# PCA_0006_Mini_CB_Servo_REV_B.net
KiCad netlist of a schematic drawn in Altium Designer
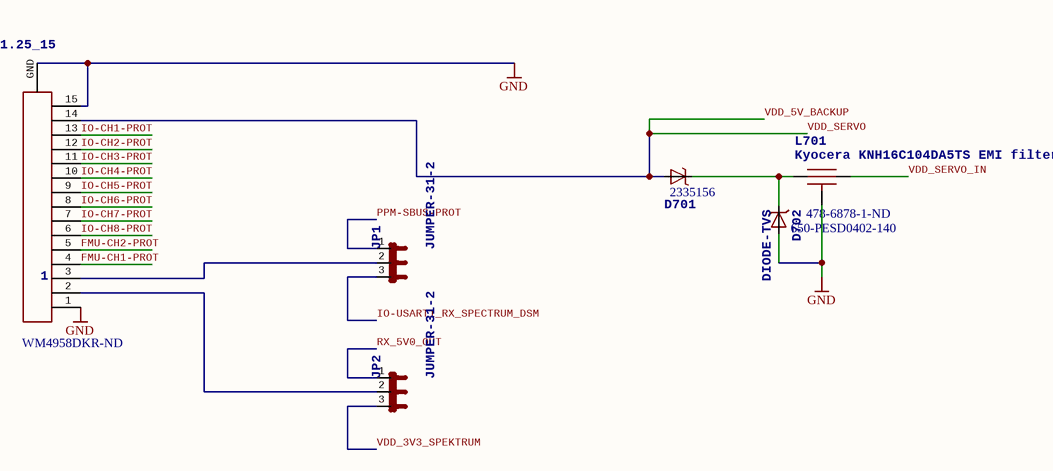
[diagram p0: PCA_0006_Mini_CB_Servo_REV_B.SchDoc]

(export (version "E")
  (design (tool "Eeschema 10.0.6"))
  (components
    (comp (ref "1")
      (value "CLICKMATE_1.25_15")
      (footprint "CLICKMATE_H15")
      (description "Connector, Receptacle, 15Pos, 1.25MM, R/A, SMD, Tin")
      (fields (field (name "SUPPLIER PART NUMBER 1") "WM4958DKR-ND") (field (name "3DR_PARTNO") "ECM0530"))
      (libsource (lib "PCA_0006_Mini_CB_REV_A") (part "CLICKMATE_1.25_15"))
    )
    (comp (ref "D701")
      (value "Schottky barrier diode in DO214AC, e.g. Fairchild SS14.")
      (footprint "MICROSMP")
      (description "Diode, Schottky, 40V, 1A, MicroSMP, SMD")
      (fields
        (field (name "PARTNUMBER") "MSS1P4-M3/89A")
        (field (name "SUPPLIER PART NUMBER 1") "2335156")
        (field (name "3DR_PARTNO") "ECM0900")
      )
      (libsource (lib "PCA_0006_Mini_CB_REV_A") (part "DIODE-SCHOTTKY_MSMP"))
    )
    (comp (ref "D702")
      (value "DIODE-TVS")
      (footprint "0402-TVS")
      (description "Diode, TVS, 14VWM, 40VC, 0402, SMD")
      (fields
        (field (name "SUPPLIER PART NUMBER 1") "650-PESD0402-140")
        (field (name "3DR_PARTNO") "ECM0837")
      )
      (libsource (lib "PCA_0006_Mini_CB_REV_A") (part "DIODE-TVS"))
    )
    (comp (ref "JP1")
      (value "JUMPER-31-2")
      (footprint "SJ_3_PASTE1&2")
      (description "DO NOT FIT")
      (libsource (lib "PCA_0006_Mini_CB_REV_A") (part "JUMPER-31-2"))
    )
    (comp (ref "JP2")
      (value "JUMPER-31-2")
      (footprint "SJ_3_PASTE1&2")
      (description "DO NOT FIT")
      (libsource (lib "PCA_0006_Mini_CB_REV_A") (part "JUMPER-31-2"))
    )
    (comp (ref "L701")
      (value "Kyocera KNH16C104DA5TS EMI filter")
      (footprint "KYOCERA-KNH16-DA")
      (description "Capacitor, Filter, 0.1uF, 25V, 2A, 0603, SMD")
      (fields (field (name "SUPPLIER PART NUMBER 1") "478-6878-1-ND") (field (name "3DR_PARTNO") "ECM0719"))
      (libsource (lib "PCA_0006_Mini_CB_REV_A") (part "KNH16C104DA5TS"))
    )
  )
  (nets
    (net (code "1") (name "/FMU-CH1-PROT") (class "Default")
      (node (ref "1") (pin "4") (pinfunction "4_4") (pintype "passive"))
    )
    (net (code "2") (name "/FMU-CH2-PROT") (class "Default")
      (node (ref "1") (pin "5") (pinfunction "5_5") (pintype "passive"))
    )
    (net (code "3") (name "/IO-CH1-PROT") (class "Default")
      (node (ref "1") (pin "13") (pinfunction "13_13") (pintype "passive"))
    )
    (net (code "4") (name "/IO-CH2-PROT") (class "Default")
      (node (ref "1") (pin "12") (pinfunction "12_12") (pintype "passive"))
    )
    (net (code "5") (name "/IO-CH3-PROT") (class "Default")
      (node (ref "1") (pin "11") (pinfunction "11_11") (pintype "passive"))
    )
    (net (code "6") (name "/IO-CH4-PROT") (class "Default")
      (node (ref "1") (pin "10") (pinfunction "10_10") (pintype "passive"))
    )
    (net (code "7") (name "/IO-CH5-PROT") (class "Default")
      (node (ref "1") (pin "9") (pinfunction "9_9") (pintype "passive"))
    )
    (net (code "8") (name "/IO-CH6-PROT") (class "Default")
      (node (ref "1") (pin "8") (pinfunction "8_8") (pintype "passive"))
    )
    (net (code "9") (name "/IO-CH7-PROT") (class "Default")
      (node (ref "1") (pin "7") (pinfunction "7_7") (pintype "passive"))
    )
    (net (code "10") (name "/IO-CH8-PROT") (class "Default")
      (node (ref "1") (pin "6") (pinfunction "6_6") (pintype "passive"))
    )
    (net (code "11") (name "/IO-USART1_RX_SPECTRUM_DSM") (class "Default")
      (node (ref "JP1") (pin "3") (pinfunction "3_3") (pintype "passive"))
    )
    (net (code "12") (name "/PPM-SBUS-PROT") (class "Default")
      (node (ref "JP1") (pin "1") (pinfunction "1_1") (pintype "passive"))
    )
    (net (code "13") (name "/RX_5V0_OUT") (class "Default")
      (node (ref "JP2") (pin "1") (pinfunction "1_1") (pintype "passive"))
    )
    (net (code "14") (name "/VDD_3V3_SPEKTRUM") (class "Default")
      (node (ref "JP2") (pin "3") (pinfunction "3_3") (pintype "passive"))
    )
    (net (code "15") (name "/VDD_5V_BACKUP") (class "Default")
      (node (ref "1") (pin "14") (pinfunction "14_14") (pintype "passive"))
      (node (ref "D701") (pin "ANODE") (pinfunction "A_ANODE") (pintype "passive"))
    )
    (net (code "16") (name "/VDD_SERVO_IN") (class "Default")
      (node (ref "L701") (pin "P$2") (pinfunction "P$2_P$2") (pintype "passive"))
    )
    (net (code "17") (name "GND") (class "Default")
      (node (ref "1") (pin "1") (pinfunction "1_1") (pintype "passive"))
      (node (ref "1") (pin "15") (pinfunction "15_15") (pintype "passive"))
      (node (ref "1") (pin "GND") (pinfunction "GND_GND") (pintype "passive"))
      (node (ref "D702") (pin "A") (pinfunction "A_A") (pintype "passive"))
      (node (ref "L701") (pin "GND") (pinfunction "GND_GND") (pintype "passive"))
    )
    (net (code "18") (name "Net-(1-Pad2)") (class "Default")
      (node (ref "1") (pin "2") (pinfunction "2_2") (pintype "passive"))
      (node (ref "JP2") (pin "2") (pinfunction "2_2") (pintype "passive"))
    )
    (net (code "19") (name "Net-(1-Pad3)") (class "Default")
      (node (ref "1") (pin "3") (pinfunction "3_3") (pintype "passive"))
      (node (ref "JP1") (pin "2") (pinfunction "2_2") (pintype "passive"))
    )
    (net (code "20") (name "Net-(D701-C)") (class "Default")
      (node (ref "D701") (pin "CATHODE") (pinfunction "C_CATHODE") (pintype "passive"))
      (node (ref "D702") (pin "C") (pinfunction "C_C") (pintype "passive"))
      (node (ref "L701") (pin "P$1") (pinfunction "P$1_P$1") (pintype "passive"))
    )
  )
)
